# STM32F446ZEJx-SW308-UFO_V1_0.net
KiCad netlist of a schematic drawn in EAGLE
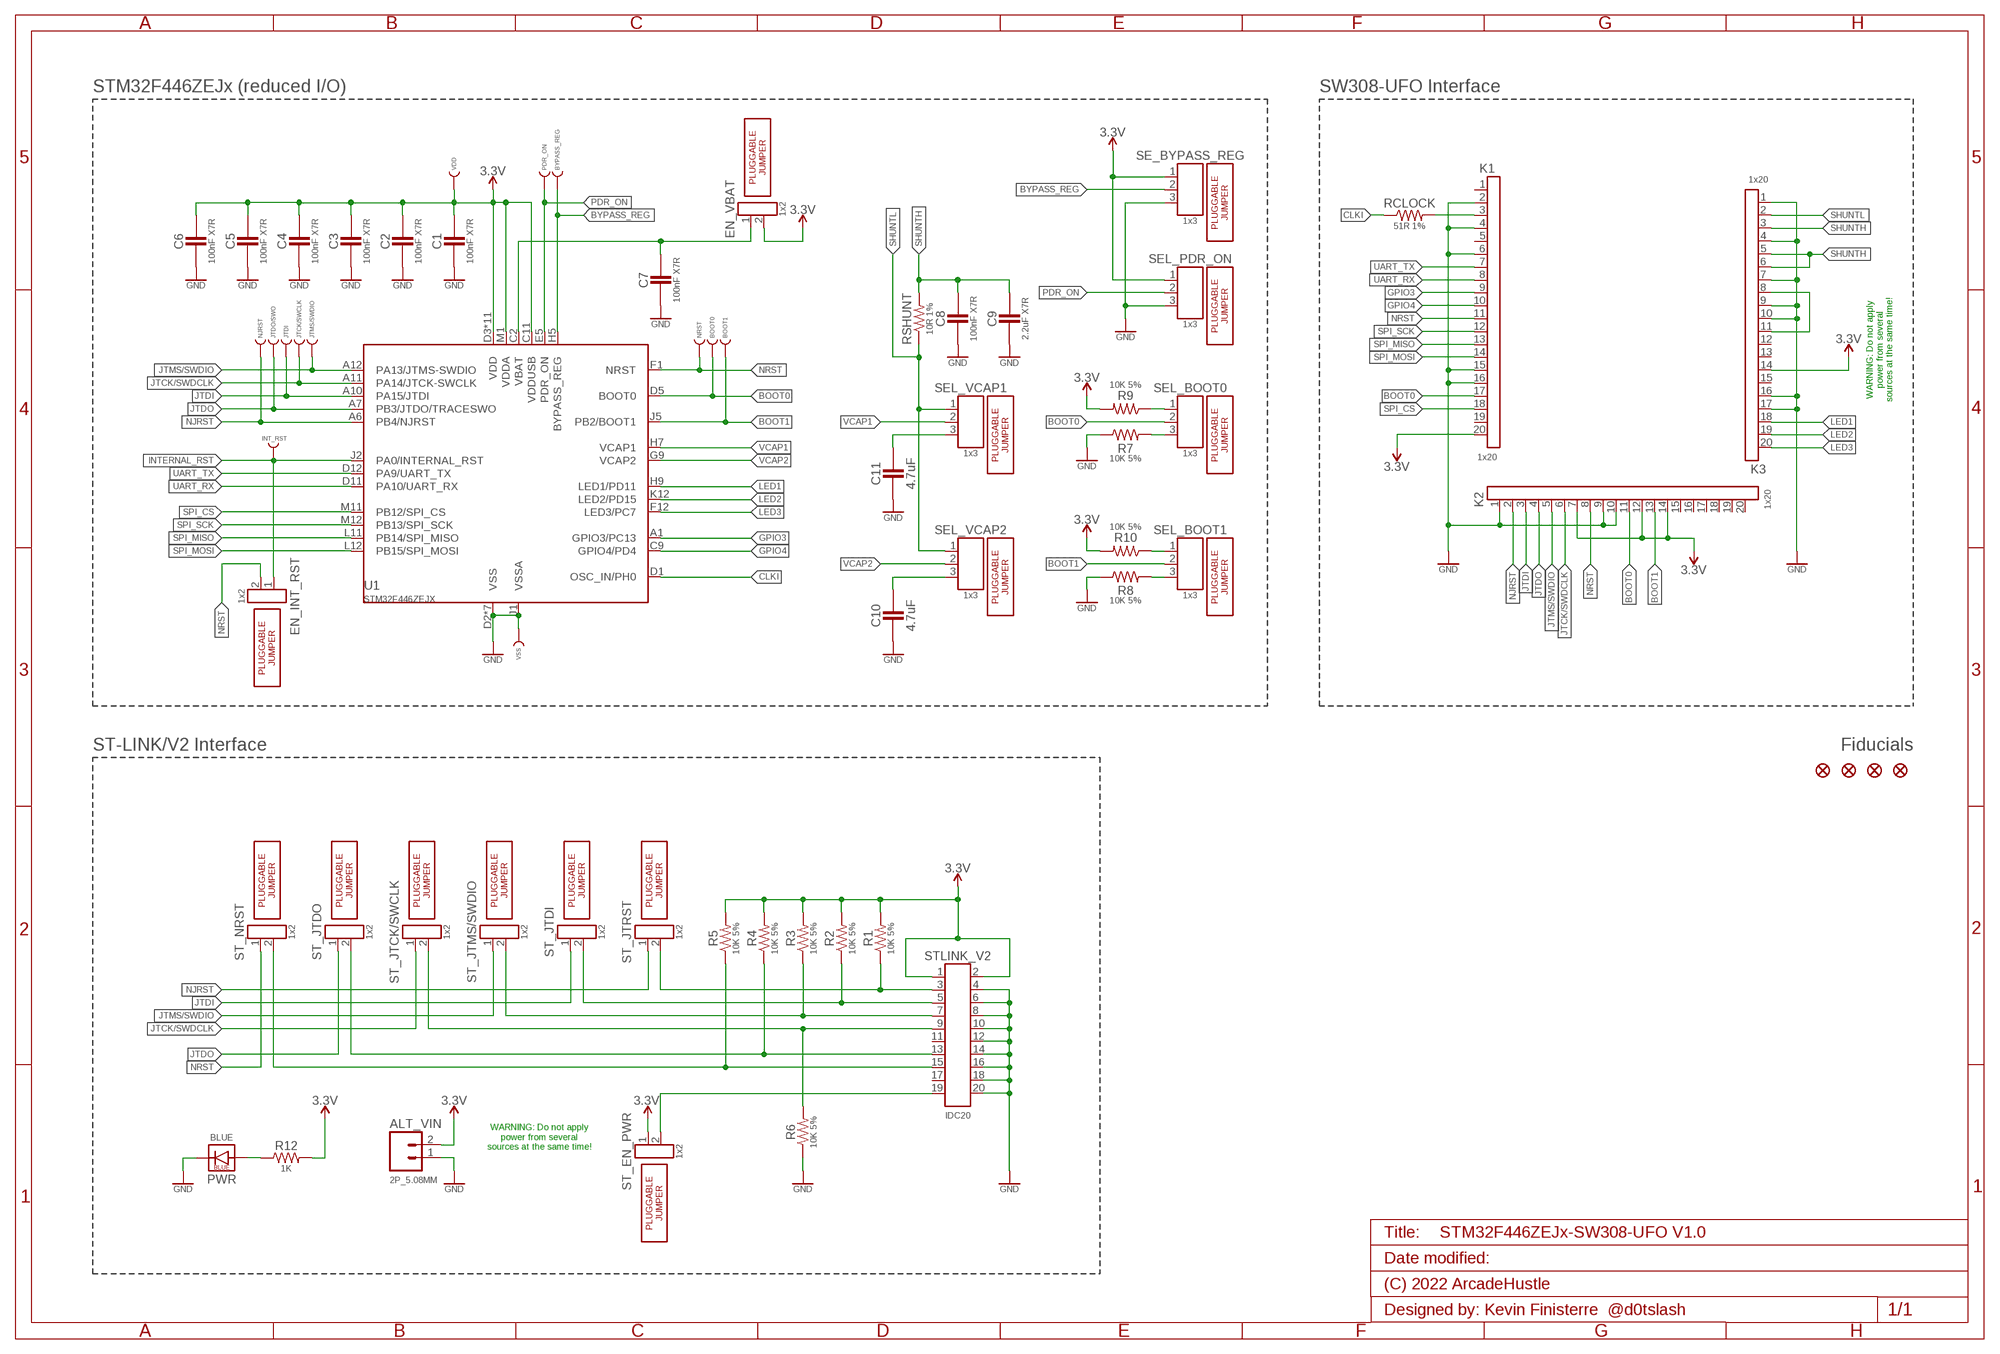
[diagram p0: schematic, sheet 1]

(export (version "E")
  (design (tool "Eeschema 10.0.6"))
  (components
    (comp (ref "ALT_VIN")
      (value "2P_5.08MM")
      (footprint "eagle-import:BORNA_2X5.08MM_NINGBO-KANGNEX-ELEC_WJ500V-5.08-2P")
      (fields (field (name "MANUFACTURER") "Ningbo Kangnex Elec"))
      (libsource (lib "eagle-import") (part "M02_BORNA_2X5.08MM_NINGBO-KANGNEX-ELEC_WJ500V-5.08-2P"))
    )
    (comp (ref "BOOT0")
      (value "TESTPOINT_TH_0.8MM")
      (footprint "eagle-import:1X01")
      (libsource (lib "eagle-import") (part "TESTPOINT_TH_0.8MM"))
    )
    (comp (ref "BOOT1")
      (value "TESTPOINT_TH_0.8MM")
      (footprint "eagle-import:1X01")
      (libsource (lib "eagle-import") (part "TESTPOINT_TH_0.8MM"))
    )
    (comp (ref "BYPASS_REG")
      (value "TESTPOINT_TH_0.8MM")
      (footprint "eagle-import:1X01")
      (libsource (lib "eagle-import") (part "TESTPOINT_TH_0.8MM"))
    )
    (comp (ref "C1")
      (value "100nF X7R")
      (footprint "eagle-import:0603_IPC_NOMINAL")
      (fields (field (name "MANUFACTURER") "Samsung Electro-Mechanics"))
      (libsource (lib "eagle-import") (part "CAP__0603_IPC_NOMINAL"))
    )
    (comp (ref "C2")
      (value "100nF X7R")
      (footprint "eagle-import:0603_IPC_NOMINAL")
      (fields (field (name "MANUFACTURER") "Samsung Electro-Mechanics"))
      (libsource (lib "eagle-import") (part "CAP__0603_IPC_NOMINAL"))
    )
    (comp (ref "C3")
      (value "100nF X7R")
      (footprint "eagle-import:0603_IPC_NOMINAL")
      (fields (field (name "MANUFACTURER") "Samsung Electro-Mechanics"))
      (libsource (lib "eagle-import") (part "CAP__0603_IPC_NOMINAL"))
    )
    (comp (ref "C4")
      (value "100nF X7R")
      (footprint "eagle-import:0603_IPC_NOMINAL")
      (fields (field (name "MANUFACTURER") "Samsung Electro-Mechanics"))
      (libsource (lib "eagle-import") (part "CAP__0603_IPC_NOMINAL"))
    )
    (comp (ref "C5")
      (value "100nF X7R")
      (footprint "eagle-import:0603_IPC_NOMINAL")
      (fields (field (name "MANUFACTURER") "Samsung Electro-Mechanics"))
      (libsource (lib "eagle-import") (part "CAP__0603_IPC_NOMINAL"))
    )
    (comp (ref "C6")
      (value "100nF X7R")
      (footprint "eagle-import:0603_IPC_NOMINAL")
      (fields (field (name "MANUFACTURER") "Samsung Electro-Mechanics"))
      (libsource (lib "eagle-import") (part "CAP__0603_IPC_NOMINAL"))
    )
    (comp (ref "C7")
      (value "100nF X7R")
      (footprint "eagle-import:0603_IPC_NOMINAL")
      (fields (field (name "MANUFACTURER") "Samsung Electro-Mechanics"))
      (libsource (lib "eagle-import") (part "CAP__0603_IPC_NOMINAL"))
    )
    (comp (ref "C8")
      (value "100nF X7R")
      (footprint "eagle-import:0603_IPC_NOMINAL")
      (fields (field (name "MANUFACTURER") "Samsung Electro-Mechanics"))
      (libsource (lib "eagle-import") (part "CAP__0603_IPC_NOMINAL"))
    )
    (comp (ref "C9")
      (value "2.2uF X7R")
      (footprint "eagle-import:0603_IPC_NOMINAL")
      (fields (field (name "MANUFACTURER") "Samsung Electro-Mechanics"))
      (libsource (lib "eagle-import") (part "CAP__0603_IPC_NOMINAL"))
    )
    (comp (ref "C10")
      (value "4.7uF")
      (footprint "eagle-import:0603_IPC_NOMINAL")
      (fields (field (name "MANUFACTURER") "Samsung Electro-Mechanics"))
      (libsource (lib "eagle-import") (part "CAP__0603_IPC_NOMINAL"))
    )
    (comp (ref "C11")
      (value "4.7uF")
      (footprint "eagle-import:0603_IPC_NOMINAL")
      (fields (field (name "MANUFACTURER") "Samsung Electro-Mechanics"))
      (libsource (lib "eagle-import") (part "CAP__0603_IPC_NOMINAL"))
    )
    (comp (ref "EN_INT_RST")
      (value "1x2")
      (footprint "eagle-import:M1X2_GREENCONN_GPHA101-0201A001A1BA(A=6,B=3)_ALT_PADS")
      (fields (field (name "MANUFACTURER") "Ckmtw(Shenzhen Cankemeng)"))
      (libsource (lib "eagle-import") (part "M1X2_GREENCONN_GPHA101-0201A001A1BA(A=6,B=3)_ALT_PADS"))
    )
    (comp (ref "EN_VBAT")
      (value "1x2")
      (footprint "eagle-import:M1X2_GREENCONN_GPHA101-0201A001A1BA(A=6,B=3)_ALT_PADS")
      (fields (field (name "MANUFACTURER") "Ckmtw(Shenzhen Cankemeng)"))
      (libsource (lib "eagle-import") (part "M1X2_GREENCONN_GPHA101-0201A001A1BA(A=6,B=3)_ALT_PADS"))
    )
    (comp (ref "FD1")
      (value "FIDUCIAL_MICRO")
      (footprint "eagle-import:FIDUCIAL-MICRO")
      (libsource (lib "eagle-import") (part "FIDUCIAL_MICRO"))
    )
    (comp (ref "FD5")
      (value "FIDUCIAL_MICRO")
      (footprint "eagle-import:FIDUCIAL-MICRO")
      (libsource (lib "eagle-import") (part "FIDUCIAL_MICRO"))
    )
    (comp (ref "FD7")
      (value "FIDUCIAL_MICRO")
      (footprint "eagle-import:FIDUCIAL-MICRO")
      (libsource (lib "eagle-import") (part "FIDUCIAL_MICRO"))
    )
    (comp (ref "FD9")
      (value "FIDUCIAL_MICRO")
      (footprint "eagle-import:FIDUCIAL-MICRO")
      (libsource (lib "eagle-import") (part "FIDUCIAL_MICRO"))
    )
    (comp (ref "INT_RST")
      (value "TESTPOINT_TH_0.8MM")
      (footprint "eagle-import:1X01")
      (libsource (lib "eagle-import") (part "TESTPOINT_TH_0.8MM"))
    )
    (comp (ref "JTCK/SWCLK")
      (value "TESTPOINT_TH_0.8MM")
      (footprint "eagle-import:1X01")
      (libsource (lib "eagle-import") (part "TESTPOINT_TH_0.8MM"))
    )
    (comp (ref "JTDI")
      (value "TESTPOINT_TH_0.8MM")
      (footprint "eagle-import:1X01")
      (libsource (lib "eagle-import") (part "TESTPOINT_TH_0.8MM"))
    )
    (comp (ref "JTDO/SWO")
      (value "TESTPOINT_TH_0.8MM")
      (footprint "eagle-import:1X01")
      (libsource (lib "eagle-import") (part "TESTPOINT_TH_0.8MM"))
    )
    (comp (ref "JTMS/SWDIO")
      (value "TESTPOINT_TH_0.8MM")
      (footprint "eagle-import:1X01")
      (libsource (lib "eagle-import") (part "TESTPOINT_TH_0.8MM"))
    )
    (comp (ref "JUMPER1")
      (value "JUMPER_2.54MM")
      (footprint "eagle-import:JUMPER_2.54MM")
      (fields (field (name "MANUFACTURER") "BOOMELE(Boom Precision Elec)"))
      (libsource (lib "eagle-import") (part "JUMPER_2.54MM"))
    )
    (comp (ref "JUMPER2")
      (value "JUMPER_2.54MM")
      (footprint "eagle-import:JUMPER_2.54MM")
      (fields (field (name "MANUFACTURER") "BOOMELE(Boom Precision Elec)"))
      (libsource (lib "eagle-import") (part "JUMPER_2.54MM"))
    )
    (comp (ref "JUMPER3")
      (value "JUMPER_2.54MM")
      (footprint "eagle-import:JUMPER_2.54MM")
      (fields (field (name "MANUFACTURER") "BOOMELE(Boom Precision Elec)"))
      (libsource (lib "eagle-import") (part "JUMPER_2.54MM"))
    )
    (comp (ref "JUMPER4")
      (value "JUMPER_2.54MM")
      (footprint "eagle-import:JUMPER_2.54MM")
      (fields (field (name "MANUFACTURER") "BOOMELE(Boom Precision Elec)"))
      (libsource (lib "eagle-import") (part "JUMPER_2.54MM"))
    )
    (comp (ref "JUMPER5")
      (value "JUMPER_2.54MM")
      (footprint "eagle-import:JUMPER_2.54MM")
      (fields (field (name "MANUFACTURER") "BOOMELE(Boom Precision Elec)"))
      (libsource (lib "eagle-import") (part "JUMPER_2.54MM"))
    )
    (comp (ref "JUMPER6")
      (value "JUMPER_2.54MM")
      (footprint "eagle-import:JUMPER_2.54MM")
      (fields (field (name "MANUFACTURER") "BOOMELE(Boom Precision Elec)"))
      (libsource (lib "eagle-import") (part "JUMPER_2.54MM"))
    )
    (comp (ref "JUMPER7")
      (value "JUMPER_2.54MM")
      (footprint "eagle-import:JUMPER_2.54MM")
      (fields (field (name "MANUFACTURER") "BOOMELE(Boom Precision Elec)"))
      (libsource (lib "eagle-import") (part "JUMPER_2.54MM"))
    )
    (comp (ref "JUMPER8")
      (value "JUMPER_2.54MM")
      (footprint "eagle-import:JUMPER_2.54MM")
      (fields (field (name "MANUFACTURER") "BOOMELE(Boom Precision Elec)"))
      (libsource (lib "eagle-import") (part "JUMPER_2.54MM"))
    )
    (comp (ref "JUMPER9")
      (value "JUMPER_2.54MM")
      (footprint "eagle-import:JUMPER_2.54MM")
      (fields (field (name "MANUFACTURER") "BOOMELE(Boom Precision Elec)"))
      (libsource (lib "eagle-import") (part "JUMPER_2.54MM"))
    )
    (comp (ref "JUMPER10")
      (value "JUMPER_2.54MM")
      (footprint "eagle-import:JUMPER_2.54MM")
      (fields (field (name "MANUFACTURER") "BOOMELE(Boom Precision Elec)"))
      (libsource (lib "eagle-import") (part "JUMPER_2.54MM"))
    )
    (comp (ref "JUMPER11")
      (value "JUMPER_2.54MM")
      (footprint "eagle-import:JUMPER_2.54MM")
      (fields (field (name "MANUFACTURER") "BOOMELE(Boom Precision Elec)"))
      (libsource (lib "eagle-import") (part "JUMPER_2.54MM"))
    )
    (comp (ref "JUMPER12")
      (value "JUMPER_2.54MM")
      (footprint "eagle-import:JUMPER_2.54MM")
      (fields (field (name "MANUFACTURER") "BOOMELE(Boom Precision Elec)"))
      (libsource (lib "eagle-import") (part "JUMPER_2.54MM"))
    )
    (comp (ref "JUMPER13")
      (value "JUMPER_2.54MM")
      (footprint "eagle-import:JUMPER_2.54MM")
      (fields (field (name "MANUFACTURER") "BOOMELE(Boom Precision Elec)"))
      (libsource (lib "eagle-import") (part "JUMPER_2.54MM"))
    )
    (comp (ref "JUMPER14")
      (value "JUMPER_2.54MM")
      (footprint "eagle-import:JUMPER_2.54MM")
      (fields (field (name "MANUFACTURER") "BOOMELE(Boom Precision Elec)"))
      (libsource (lib "eagle-import") (part "JUMPER_2.54MM"))
    )
    (comp (ref "JUMPER15")
      (value "JUMPER_2.54MM")
      (footprint "eagle-import:JUMPER_2.54MM")
      (fields (field (name "MANUFACTURER") "BOOMELE(Boom Precision Elec)"))
      (libsource (lib "eagle-import") (part "JUMPER_2.54MM"))
    )
    (comp (ref "K1")
      (value "1x20")
      (footprint "eagle-import:M1X20_2.54MM_LOCK_BOOMELE_C50981")
      (fields (field (name "MANUFACTURER") "BOOMELE(Boom Precision Elec)"))
      (libsource (lib "eagle-import") (part "M1X20_2.54MM_LOCK_BOOMELE_C50981"))
    )
    (comp (ref "K2")
      (value "1x20")
      (footprint "eagle-import:M1X20_2.54MM_LOCK_BOOMELE_C50981")
      (fields (field (name "MANUFACTURER") "BOOMELE(Boom Precision Elec)"))
      (libsource (lib "eagle-import") (part "M1X20_2.54MM_LOCK_BOOMELE_C50981"))
    )
    (comp (ref "K3")
      (value "1x20")
      (footprint "eagle-import:M1X20_2.54MM_LOCK_BOOMELE_C50981")
      (fields (field (name "MANUFACTURER") "BOOMELE(Boom Precision Elec)"))
      (libsource (lib "eagle-import") (part "M1X20_2.54MM_LOCK_BOOMELE_C50981"))
    )
    (comp (ref "NJRST")
      (value "TESTPOINT_TH_0.8MM")
      (footprint "eagle-import:1X01")
      (libsource (lib "eagle-import") (part "TESTPOINT_TH_0.8MM"))
    )
    (comp (ref "NRST")
      (value "TESTPOINT_TH_0.8MM")
      (footprint "eagle-import:1X01")
      (libsource (lib "eagle-import") (part "TESTPOINT_TH_0.8MM"))
    )
    (comp (ref "PDR_ON")
      (value "TESTPOINT_TH_0.8MM")
      (footprint "eagle-import:1X01")
      (libsource (lib "eagle-import") (part "TESTPOINT_TH_0.8MM"))
    )
    (comp (ref "PWR")
      (value "BLUE")
      (footprint "eagle-import:0603-BLUE-LED")
      (fields (field (name "MANUFACTURER") "Everlight Elec"))
      (libsource (lib "eagle-import") (part "DIODE-BLUE_0603"))
    )
    (comp (ref "R1")
      (value "10K 5%")
      (footprint "eagle-import:0603_IPC_NOMINAL")
      (fields (field (name "MANUFACTURER") "YAGEO"))
      (libsource (lib "eagle-import") (part "R_US_0603_IPC_NOMINAL"))
    )
    (comp (ref "R2")
      (value "10K 5%")
      (footprint "eagle-import:0603_IPC_NOMINAL")
      (fields (field (name "MANUFACTURER") "YAGEO"))
      (libsource (lib "eagle-import") (part "R_US_0603_IPC_NOMINAL"))
    )
    (comp (ref "R3")
      (value "10K 5%")
      (footprint "eagle-import:0603_IPC_NOMINAL")
      (fields (field (name "MANUFACTURER") "YAGEO"))
      (libsource (lib "eagle-import") (part "R_US_0603_IPC_NOMINAL"))
    )
    (comp (ref "R4")
      (value "10K 5%")
      (footprint "eagle-import:0603_IPC_NOMINAL")
      (fields (field (name "MANUFACTURER") "YAGEO"))
      (libsource (lib "eagle-import") (part "R_US_0603_IPC_NOMINAL"))
    )
    (comp (ref "R5")
      (value "10K 5%")
      (footprint "eagle-import:0603_IPC_NOMINAL")
      (fields (field (name "MANUFACTURER") "YAGEO"))
      (libsource (lib "eagle-import") (part "R_US_0603_IPC_NOMINAL"))
    )
    (comp (ref "R6")
      (value "10K 5%")
      (footprint "eagle-import:0603_IPC_NOMINAL")
      (fields (field (name "MANUFACTURER") "YAGEO"))
      (libsource (lib "eagle-import") (part "R_US_0603_IPC_NOMINAL"))
    )
    (comp (ref "R7")
      (value "10K 5%")
      (footprint "eagle-import:0603_IPC_NOMINAL")
      (fields (field (name "MANUFACTURER") "YAGEO"))
      (libsource (lib "eagle-import") (part "R_US_0603_IPC_NOMINAL"))
    )
    (comp (ref "R8")
      (value "10K 5%")
      (footprint "eagle-import:0603_IPC_NOMINAL")
      (fields (field (name "MANUFACTURER") "YAGEO"))
      (libsource (lib "eagle-import") (part "R_US_0603_IPC_NOMINAL"))
    )
    (comp (ref "R9")
      (value "10K 5%")
      (footprint "eagle-import:0603_IPC_NOMINAL")
      (fields (field (name "MANUFACTURER") "YAGEO"))
      (libsource (lib "eagle-import") (part "R_US_0603_IPC_NOMINAL"))
    )
    (comp (ref "R10")
      (value "10K 5%")
      (footprint "eagle-import:0603_IPC_NOMINAL")
      (fields (field (name "MANUFACTURER") "YAGEO"))
      (libsource (lib "eagle-import") (part "R_US_0603_IPC_NOMINAL"))
    )
    (comp (ref "R12")
      (value "1K")
      (footprint "eagle-import:0603_IPC_NOMINAL")
      (fields (field (name "MANUFACTURER") "YAGEO"))
      (libsource (lib "eagle-import") (part "R_US_0603_IPC_NOMINAL"))
    )
    (comp (ref "RCLOCK")
      (value "51R 1%")
      (footprint "eagle-import:0603_IPC_NOMINAL")
      (fields (field (name "MANUFACTURER") "YAGEO"))
      (libsource (lib "eagle-import") (part "R_US_0603_IPC_NOMINAL"))
    )
    (comp (ref "RSHUNT")
      (value "10R 1%")
      (footprint "eagle-import:0603_IPC_NOMINAL")
      (fields (field (name "MANUFACTURER") "YAGEO"))
      (libsource (lib "eagle-import") (part "R_US_0603_IPC_NOMINAL"))
    )
    (comp (ref "SEL_BOOT0")
      (value "1x3")
      (footprint "eagle-import:M1X3_GREENCONN_GPHA101-0301A001A1BA(A=6,B=3)_ALT_PADS")
      (fields (field (name "MANUFACTURER") "BOOMELE(Boom Precision Elec)"))
      (libsource (lib "eagle-import") (part "M3_GREENCONN_GPHA101-0301A001A1BA(A=6,B=3)_ALT_PADS"))
    )
    (comp (ref "SEL_BOOT1")
      (value "1x3")
      (footprint "eagle-import:M1X3_GREENCONN_GPHA101-0301A001A1BA(A=6,B=3)_ALT_PADS")
      (fields (field (name "MANUFACTURER") "BOOMELE(Boom Precision Elec)"))
      (libsource (lib "eagle-import") (part "M3_GREENCONN_GPHA101-0301A001A1BA(A=6,B=3)_ALT_PADS"))
    )
    (comp (ref "SEL_PDR_ON")
      (value "1x3")
      (footprint "eagle-import:M1X3_GREENCONN_GPHA101-0301A001A1BA(A=6,B=3)_ALT_PADS")
      (fields (field (name "MANUFACTURER") "BOOMELE(Boom Precision Elec)"))
      (libsource (lib "eagle-import") (part "M3_GREENCONN_GPHA101-0301A001A1BA(A=6,B=3)_ALT_PADS"))
    )
    (comp (ref "SEL_VCAP1")
      (value "1x3")
      (footprint "eagle-import:M1X3_GREENCONN_GPHA101-0301A001A1BA(A=6,B=3)_ALT_PADS")
      (fields (field (name "MANUFACTURER") "BOOMELE(Boom Precision Elec)"))
      (libsource (lib "eagle-import") (part "M3_GREENCONN_GPHA101-0301A001A1BA(A=6,B=3)_ALT_PADS"))
    )
    (comp (ref "SEL_VCAP2")
      (value "1x3")
      (footprint "eagle-import:M1X3_GREENCONN_GPHA101-0301A001A1BA(A=6,B=3)_ALT_PADS")
      (fields (field (name "MANUFACTURER") "BOOMELE(Boom Precision Elec)"))
      (libsource (lib "eagle-import") (part "M3_GREENCONN_GPHA101-0301A001A1BA(A=6,B=3)_ALT_PADS"))
    )
    (comp (ref "SE_BYPASS_REG")
      (value "1x3")
      (footprint "eagle-import:M1X3_GREENCONN_GPHA101-0301A001A1BA(A=6,B=3)_ALT_PADS")
      (fields (field (name "MANUFACTURER") "BOOMELE(Boom Precision Elec)"))
      (libsource (lib "eagle-import") (part "M3_GREENCONN_GPHA101-0301A001A1BA(A=6,B=3)_ALT_PADS"))
    )
    (comp (ref "STLINK_V2")
      (value "IDC20")
      (footprint "eagle-import:M2X10_2.54MM_IDC_SHROUDED__JLIN_321020SG0ABK00A01_C429961")
      (fields (field (name "MANUFACTURER") "JLIN"))
      (libsource (lib "eagle-import") (part "M2X10_2.54MM_IDC_SHROUDED__JLIN_321020SG0ABK00A01_C429961"))
    )
    (comp (ref "ST_EN_PWR")
      (value "1x2")
      (footprint "eagle-import:M1X2_GREENCONN_GPHA101-0201A001A1BA(A=6,B=3)_ALT_PADS")
      (fields (field (name "MANUFACTURER") "Ckmtw(Shenzhen Cankemeng)"))
      (libsource (lib "eagle-import") (part "M1X2_GREENCONN_GPHA101-0201A001A1BA(A=6,B=3)_ALT_PADS"))
    )
    (comp (ref "ST_JTCK/SWCLK")
      (value "1x2")
      (footprint "eagle-import:M1X2_GREENCONN_GPHA101-0201A001A1BA(A=6,B=3)_ALT_PADS")
      (fields (field (name "MANUFACTURER") "Ckmtw(Shenzhen Cankemeng)"))
      (libsource (lib "eagle-import") (part "M1X2_GREENCONN_GPHA101-0201A001A1BA(A=6,B=3)_ALT_PADS"))
    )
    (comp (ref "ST_JTDI")
      (value "1x2")
      (footprint "eagle-import:M1X2_GREENCONN_GPHA101-0201A001A1BA(A=6,B=3)_ALT_PADS")
      (fields (field (name "MANUFACTURER") "Ckmtw(Shenzhen Cankemeng)"))
      (libsource (lib "eagle-import") (part "M1X2_GREENCONN_GPHA101-0201A001A1BA(A=6,B=3)_ALT_PADS"))
    )
    (comp (ref "ST_JTDO")
      (value "1x2")
      (footprint "eagle-import:M1X2_GREENCONN_GPHA101-0201A001A1BA(A=6,B=3)_ALT_PADS")
      (fields (field (name "MANUFACTURER") "Ckmtw(Shenzhen Cankemeng)"))
      (libsource (lib "eagle-import") (part "M1X2_GREENCONN_GPHA101-0201A001A1BA(A=6,B=3)_ALT_PADS"))
    )
    (comp (ref "ST_JTMS/SWDIO")
      (value "1x2")
      (footprint "eagle-import:M1X2_GREENCONN_GPHA101-0201A001A1BA(A=6,B=3)_ALT_PADS")
      (fields (field (name "MANUFACTURER") "Ckmtw(Shenzhen Cankemeng)"))
      (libsource (lib "eagle-import") (part "M1X2_GREENCONN_GPHA101-0201A001A1BA(A=6,B=3)_ALT_PADS"))
    )
    (comp (ref "ST_JTRST")
      (value "1x2")
      (footprint "eagle-import:M1X2_GREENCONN_GPHA101-0201A001A1BA(A=6,B=3)_ALT_PADS")
      (fields (field (name "MANUFACTURER") "Ckmtw(Shenzhen Cankemeng)"))
      (libsource (lib "eagle-import") (part "M1X2_GREENCONN_GPHA101-0201A001A1BA(A=6,B=3)_ALT_PADS"))
    )
    (comp (ref "ST_NRST")
      (value "1x2")
      (footprint "eagle-import:M1X2_GREENCONN_GPHA101-0201A001A1BA(A=6,B=3)_ALT_PADS")
      (fields (field (name "MANUFACTURER") "Ckmtw(Shenzhen Cankemeng)"))
      (libsource (lib "eagle-import") (part "M1X2_GREENCONN_GPHA101-0201A001A1BA(A=6,B=3)_ALT_PADS"))
    )
    (comp (ref "U1")
      (value "STM32F446ZEJX")
      (footprint "eagle-import:STM32F446ZEJX")
      (libsource (lib "eagle-import") (part "STM32F446ZEJX_MINIMUM2_UFBGA144"))
    )
    (comp (ref "VDD")
      (value "TESTPOINT_TH_0.8MM")
      (footprint "eagle-import:1X01")
      (libsource (lib "eagle-import") (part "TESTPOINT_TH_0.8MM"))
    )
    (comp (ref "VSS")
      (value "TESTPOINT_TH_0.8MM")
      (footprint "eagle-import:1X01")
      (libsource (lib "eagle-import") (part "TESTPOINT_TH_0.8MM"))
    )
  )
  (nets
    (net (code "1") (name "3.3V") (class "Default")
      (node (ref "ALT_VIN") (pin "2") (pinfunction "2_2") (pintype "passive"))
      (node (ref "C1") (pin "1") (pinfunction "1_1") (pintype "passive"))
      (node (ref "C2") (pin "1") (pinfunction "1_1") (pintype "passive"))
      (node (ref "C3") (pin "1") (pinfunction "1_1") (pintype "passive"))
      (node (ref "C4") (pin "1") (pinfunction "1_1") (pintype "passive"))
      (node (ref "C5") (pin "1") (pinfunction "1_1") (pintype "passive"))
      (node (ref "C6") (pin "1") (pinfunction "1_1") (pintype "passive"))
      (node (ref "EN_VBAT") (pin "2") (pinfunction "2_2") (pintype "bidirectional"))
      (node (ref "K1") (pin "20") (pinfunction "20_20") (pintype "bidirectional"))
      (node (ref "K2") (pin "12") (pinfunction "12_12") (pintype "bidirectional"))
      (node (ref "K2") (pin "14") (pinfunction "14_14") (pintype "bidirectional"))
      (node (ref "K2") (pin "7") (pinfunction "7_7") (pintype "bidirectional"))
      (node (ref "K3") (pin "14") (pinfunction "14_14") (pintype "bidirectional"))
      (node (ref "R1") (pin "2") (pinfunction "2_2") (pintype "passive"))
      (node (ref "R10") (pin "2") (pinfunction "2_2") (pintype "passive"))
      (node (ref "R12") (pin "2") (pinfunction "2_2") (pintype "passive"))
      (node (ref "R2") (pin "2") (pinfunction "2_2") (pintype "passive"))
      (node (ref "R3") (pin "2") (pinfunction "2_2") (pintype "passive"))
      (node (ref "R4") (pin "2") (pinfunction "2_2") (pintype "passive"))
      (node (ref "R5") (pin "2") (pinfunction "2_2") (pintype "passive"))
      (node (ref "R9") (pin "2") (pinfunction "2_2") (pintype "passive"))
      (node (ref "SEL_PDR_ON") (pin "1") (pinfunction "1_1") (pintype "bidirectional"))
      (node (ref "SE_BYPASS_REG") (pin "1") (pinfunction "1_1") (pintype "bidirectional"))
      (node (ref "STLINK_V2") (pin "1") (pinfunction "1_1") (pintype "bidirectional"))
      (node (ref "STLINK_V2") (pin "2") (pinfunction "2_2") (pintype "bidirectional"))
      (node (ref "ST_EN_PWR") (pin "1") (pinfunction "1_1") (pintype "bidirectional"))
      (node (ref "U1") (pin "C11") (pinfunction "VDDUSB_C11") (pintype "power_in"))
      (node (ref "U1") (pin "D3") (pinfunction "VDD_D3") (pintype "power_in"))
      (node (ref "U1") (pin "F10") (pinfunction "VDD_F10") (pintype "power_in"))
      (node (ref "U1") (pin "F4") (pinfunction "VDD_F4") (pintype "power_in"))
      (node (ref "U1") (pin "F5") (pinfunction "VDD_F5") (pintype "power_in"))
      (node (ref "U1") (pin "F6") (pinfunction "VDD_F6") (pintype "power_in"))
      (node (ref "U1") (pin "F7") (pinfunction "VDD_F7") (pintype "power_in"))
      (node (ref "U1") (pin "F8") (pinfunction "VDD_F8") (pintype "power_in"))
      (node (ref "U1") (pin "F9") (pinfunction "VDD_F9") (pintype "power_in"))
      (node (ref "U1") (pin "G5") (pinfunction "VDD_G5") (pintype "power_in"))
      (node (ref "U1") (pin "G6") (pinfunction "VDD_G6") (pintype "power_in"))
      (node (ref "U1") (pin "G7") (pinfunction "VDD_G7") (pintype "power_in"))
      (node (ref "U1") (pin "M1") (pinfunction "VDDA_M1") (pintype "power_in"))
      (node (ref "VDD") (pin "1") (pinfunction "1_1") (pintype "bidirectional"))
    )
    (net (code "2") (name "BOOT0") (class "Default")
      (node (ref "BOOT0") (pin "1") (pinfunction "1_1") (pintype "bidirectional"))
      (node (ref "K1") (pin "17") (pinfunction "17_17") (pintype "bidirectional"))
      (node (ref "K2") (pin "11") (pinfunction "11_11") (pintype "bidirectional"))
      (node (ref "SEL_BOOT0") (pin "2") (pinfunction "2_2") (pintype "bidirectional"))
      (node (ref "U1") (pin "D5") (pinfunction "BOOT0_D5") (pintype "bidirectional"))
    )
    (net (code "3") (name "BOOT1") (class "Default")
      (node (ref "BOOT1") (pin "1") (pinfunction "1_1") (pintype "bidirectional"))
      (node (ref "K2") (pin "13") (pinfunction "13_13") (pintype "bidirectional"))
      (node (ref "SEL_BOOT1") (pin "2") (pinfunction "2_2") (pintype "bidirectional"))
      (node (ref "U1") (pin "J5") (pinfunction "PB2/BOOT1_J5") (pintype "bidirectional"))
    )
    (net (code "4") (name "BYPASS_REG") (class "Default")
      (node (ref "BYPASS_REG") (pin "1") (pinfunction "1_1") (pintype "bidirectional"))
      (node (ref "SE_BYPASS_REG") (pin "2") (pinfunction "2_2") (pintype "bidirectional"))
      (node (ref "U1") (pin "H5") (pinfunction "BYPASS_REG_H5") (pintype "power_in"))
    )
    (net (code "5") (name "CLKI") (class "Default")
      (node (ref "RCLOCK") (pin "1") (pinfunction "1_1") (pintype "passive"))
      (node (ref "U1") (pin "D1") (pinfunction "OSC_IN/PH0_D1") (pintype "bidirectional"))
    )
    (net (code "6") (name "GND") (class "Default")
      (node (ref "ALT_VIN") (pin "1") (pinfunction "1_1") (pintype "passive"))
      (node (ref "C1") (pin "2") (pinfunction "2_2") (pintype "passive"))
      (node (ref "C10") (pin "2") (pinfunction "2_2") (pintype "passive"))
      (node (ref "C11") (pin "2") (pinfunction "2_2") (pintype "passive"))
      (node (ref "C2") (pin "2") (pinfunction "2_2") (pintype "passive"))
      (node (ref "C3") (pin "2") (pinfunction "2_2") (pintype "passive"))
      (node (ref "C4") (pin "2") (pinfunction "2_2") (pintype "passive"))
      (node (ref "C5") (pin "2") (pinfunction "2_2") (pintype "passive"))
      (node (ref "C6") (pin "2") (pinfunction "2_2") (pintype "passive"))
      (node (ref "C7") (pin "2") (pinfunction "2_2") (pintype "passive"))
      (node (ref "C8") (pin "2") (pinfunction "2_2") (pintype "passive"))
      (node (ref "C9") (pin "2") (pinfunction "2_2") (pintype "passive"))
      (node (ref "K1") (pin "15") (pinfunction "15_15") (pintype "bidirectional"))
      (node (ref "K1") (pin "16") (pinfunction "16_16") (pintype "bidirectional"))
      (node (ref "K1") (pin "2") (pinfunction "2_2") (pintype "bidirectional"))
      (node (ref "K1") (pin "4") (pinfunction "4_4") (pintype "bidirectional"))
      (node (ref "K1") (pin "6") (pinfunction "6_6") (pintype "bidirectional"))
      (node (ref "K2") (pin "1") (pinfunction "1_1") (pintype "bidirectional"))
      (node (ref "K2") (pin "10") (pinfunction "10_10") (pintype "bidirectional"))
      (node (ref "K2") (pin "9") (pinfunction "9_9") (pintype "bidirectional"))
      (node (ref "K3") (pin "1") (pinfunction "1_1") (pintype "bidirectional"))
      (node (ref "K3") (pin "10") (pinfunction "10_10") (pintype "bidirectional"))
      (node (ref "K3") (pin "16") (pinfunction "16_16") (pintype "bidirectional"))
      (node (ref "K3") (pin "17") (pinfunction "17_17") (pintype "bidirectional"))
      (node (ref "K3") (pin "4") (pinfunction "4_4") (pintype "bidirectional"))
      (node (ref "K3") (pin "7") (pinfunction "7_7") (pintype "bidirectional"))
      (node (ref "K3") (pin "9") (pinfunction "9_9") (pintype "bidirectional"))
      (node (ref "PWR") (pin "CATHODE") (pinfunction "C_CATHODE") (pintype "passive"))
      (node (ref "R6") (pin "1") (pinfunction "1_1") (pintype "passive"))
      (node (ref "R7") (pin "1") (pinfunction "1_1") (pintype "passive"))
      (node (ref "R8") (pin "1") (pinfunction "1_1") (pintype "passive"))
      (node (ref "SEL_PDR_ON") (pin "3") (pinfunction "3_3") (pintype "bidirectional"))
      (node (ref "SE_BYPASS_REG") (pin "3") (pinfunction "3_3") (pintype "bidirectional"))
      (node (ref "STLINK_V2") (pin "10") (pinfunction "10_10") (pintype "bidirectional"))
      (node (ref "STLINK_V2") (pin "12") (pinfunction "12_12") (pintype "bidirectional"))
      (node (ref "STLINK_V2") (pin "14") (pinfunction "14_14") (pintype "bidirectional"))
      (node (ref "STLINK_V2") (pin "16") (pinfunction "16_16") (pintype "bidirectional"))
      (node (ref "STLINK_V2") (pin "18") (pinfunction "18_18") (pintype "bidirectional"))
      (node (ref "STLINK_V2") (pin "20") (pinfunction "20_20") (pintype "bidirectional"))
      (node (ref "STLINK_V2") (pin "4") (pinfunction "4_4") (pintype "bidirectional"))
      (node (ref "STLINK_V2") (pin "6") (pinfunction "6_6") (pintype "bidirectional"))
      (node (ref "STLINK_V2") (pin "8") (pinfunction "8_8") (pintype "bidirectional"))
      (node (ref "U1") (pin "D2") (pinfunction "VSS_D2") (pintype "power_in"))
      (node (ref "U1") (pin "E6") (pinfunction "VSS_E6") (pintype "power_in"))
      (node (ref "U1") (pin "E7") (pinfunction "VSS_E7") (pintype "power_in"))
      (node (ref "U1") (pin "G10") (pinfunction "VSS_G10") (pintype "power_in"))
      (node (ref "U1") (pin "G4") (pinfunction "VSS_G4") (pintype "power_in"))
      (node (ref "U1") (pin "G8") (pinfunction "VSS_G8") (pintype "power_in"))
      (node (ref "U1") (pin "H6") (pinfunction "VSS_H6") (pintype "power_in"))
      (node (ref "U1") (pin "J1") (pinfunction "VSSA_J1") (pintype "power_in"))
      (node (ref "VSS") (pin "1") (pinfunction "1_1") (pintype "bidirectional"))
    )
    (net (code "7") (name "GPIO3") (class "Default")
      (node (ref "K1") (pin "9") (pinfunction "9_9") (pintype "bidirectional"))
      (node (ref "U1") (pin "A1") (pinfunction "GPIO3/PC13_A1") (pintype "bidirectional"))
    )
    (net (code "8") (name "GPIO4") (class "Default")
      (node (ref "K1") (pin "10") (pinfunction "10_10") (pintype "bidirectional"))
      (node (ref "U1") (pin "C9") (pinfunction "GPIO4/PD4_C9") (pintype "bidirectional"))
    )
    (net (code "9") (name "INTERNAL_RST") (class "Default")
      (node (ref "EN_INT_RST") (pin "1") (pinfunction "1_1") (pintype "bidirectional"))
      (node (ref "INT_RST") (pin "1") (pinfunction "1_1") (pintype "bidirectional"))
      (node (ref "U1") (pin "J2") (pinfunction "PA0/INTERNAL_RST_J2") (pintype "bidirectional"))
    )
    (net (code "10") (name "JTCK{slash}SWDCLK") (class "Default")
      (node (ref "JTCK/SWCLK") (pin "1") (pinfunction "1_1") (pintype "bidirectional"))
      (node (ref "K2") (pin "6") (pinfunction "6_6") (pintype "bidirectional"))
      (node (ref "ST_JTCK/SWCLK") (pin "1") (pinfunction "1_1") (pintype "bidirectional"))
      (node (ref "U1") (pin "A11") (pinfunction "PA14/JTCK-SWCLK_A11") (pintype "bidirectional"))
    )
    (net (code "11") (name "JTDI") (class "Default")
      (node (ref "JTDI") (pin "1") (pinfunction "1_1") (pintype "bidirectional"))
      (node (ref "K2") (pin "3") (pinfunction "3_3") (pintype "bidirectional"))
      (node (ref "ST_JTDI") (pin "1") (pinfunction "1_1") (pintype "bidirectional"))
      (node (ref "U1") (pin "A10") (pinfunction "PA15/JTDI_A10") (pintype "bidirectional"))
    )
    (net (code "12") (name "JTDO") (class "Default")
      (node (ref "JTDO/SWO") (pin "1") (pinfunction "1_1") (pintype "bidirectional"))
      (node (ref "K2") (pin "4") (pinfunction "4_4") (pintype "bidirectional"))
      (node (ref "ST_JTDO") (pin "1") (pinfunction "1_1") (pintype "bidirectional"))
      (node (ref "U1") (pin "A7") (pinfunction "PB3/JTDO/TRACESWO_A7") (pintype "bidirectional"))
    )
    (net (code "13") (name "JTMS{slash}SWDIO") (class "Default")
      (node (ref "JTMS/SWDIO") (pin "1") (pinfunction "1_1") (pintype "bidirectional"))
      (node (ref "K2") (pin "5") (pinfunction "5_5") (pintype "bidirectional"))
      (node (ref "ST_JTMS/SWDIO") (pin "1") (pinfunction "1_1") (pintype "bidirectional"))
      (node (ref "U1") (pin "A12") (pinfunction "PA13/JTMS-SWDIO_A12") (pintype "bidirectional"))
    )
    (net (code "14") (name "LED1") (class "Default")
      (node (ref "K3") (pin "18") (pinfunction "18_18") (pintype "bidirectional"))
      (node (ref "U1") (pin "H9") (pinfunction "LED1/PD11_H9") (pintype "bidirectional"))
    )
    (net (code "15") (name "LED2") (class "Default")
      (node (ref "K3") (pin "19") (pinfunction "19_19") (pintype "bidirectional"))
      (node (ref "U1") (pin "K12") (pinfunction "LED2/PD15_K12") (pintype "bidirectional"))
    )
    (net (code "16") (name "LED3") (class "Default")
      (node (ref "K3") (pin "20") (pinfunction "20_20") (pintype "bidirectional"))
      (node (ref "U1") (pin "F12") (pinfunction "LED3/PC7_F12") (pintype "bidirectional"))
    )
    (net (code "17") (name "NJRST") (class "Default")
      (node (ref "K2") (pin "2") (pinfunction "2_2") (pintype "bidirectional"))
      (node (ref "NJRST") (pin "1") (pinfunction "1_1") (pintype "bidirectional"))
      (node (ref "ST_JTRST") (pin "1") (pinfunction "1_1") (pintype "bidirectional"))
      (node (ref "U1") (pin "A6") (pinfunction "PB4/NJRST_A6") (pintype "bidirectional"))
    )
    (net (code "18") (name "NRST") (class "Default")
      (node (ref "EN_INT_RST") (pin "2") (pinfunction "2_2") (pintype "bidirectional"))
      (node (ref "K1") (pin "11") (pinfunction "11_11") (pintype "bidirectional"))
      (node (ref "K2") (pin "8") (pinfunction "8_8") (pintype "bidirectional"))
      (node (ref "NRST") (pin "1") (pinfunction "1_1") (pintype "bidirectional"))
      (node (ref "ST_NRST") (pin "1") (pinfunction "1_1") (pintype "bidirectional"))
      (node (ref "U1") (pin "F1") (pinfunction "NRST_F1") (pintype "bidirectional"))
    )
    (net (code "19") (name "Net-(C10-Pad1)") (class "Default")
      (node (ref "C10") (pin "1") (pinfunction "1_1") (pintype "passive"))
      (node (ref "SEL_VCAP2") (pin "3") (pinfunction "3_3") (pintype "bidirectional"))
    )
    (net (code "20") (name "Net-(C11-Pad1)") (class "Default")
      (node (ref "C11") (pin "1") (pinfunction "1_1") (pintype "passive"))
      (node (ref "SEL_VCAP1") (pin "3") (pinfunction "3_3") (pintype "bidirectional"))
    )
    (net (code "21") (name "Net-(K1-Pad3)") (class "Default")
      (node (ref "K1") (pin "3") (pinfunction "3_3") (pintype "bidirectional"))
      (node (ref "RCLOCK") (pin "2") (pinfunction "2_2") (pintype "passive"))
    )
    (net (code "22") (name "Net-(K3-Pad11)") (class "Default")
      (node (ref "K3") (pin "11") (pinfunction "11_11") (pintype "bidirectional"))
      (node (ref "K3") (pin "8") (pinfunction "8_8") (pintype "bidirectional"))
    )
    (net (code "23") (name "Net-(PWR-A)") (class "Default")
      (node (ref "PWR") (pin "ANODE") (pinfunction "A_ANODE") (pintype "passive"))
      (node (ref "R12") (pin "1") (pinfunction "1_1") (pintype "passive"))
    )
    (net (code "24") (name "Net-(R1-Pad1)") (class "Default")
      (node (ref "R1") (pin "1") (pinfunction "1_1") (pintype "passive"))
      (node (ref "STLINK_V2") (pin "3") (pinfunction "3_3") (pintype "bidirectional"))
      (node (ref "ST_JTRST") (pin "2") (pinfunction "2_2") (pintype "bidirectional"))
    )
    (net (code "25") (name "Net-(R2-Pad1)") (class "Default")
      (node (ref "R2") (pin "1") (pinfunction "1_1") (pintype "passive"))
      (node (ref "STLINK_V2") (pin "5") (pinfunction "5_5") (pintype "bidirectional"))
      (node (ref "ST_JTDI") (pin "2") (pinfunction "2_2") (pintype "bidirectional"))
    )
    (net (code "26") (name "Net-(R3-Pad1)") (class "Default")
      (node (ref "R3") (pin "1") (pinfunction "1_1") (pintype "passive"))
      (node (ref "STLINK_V2") (pin "7") (pinfunction "7_7") (pintype "bidirectional"))
      (node (ref "ST_JTMS/SWDIO") (pin "2") (pinfunction "2_2") (pintype "bidirectional"))
    )
    (net (code "27") (name "Net-(R4-Pad1)") (class "Default")
      (node (ref "R4") (pin "1") (pinfunction "1_1") (pintype "passive"))
      (node (ref "STLINK_V2") (pin "13") (pinfunction "13_13") (pintype "bidirectional"))
      (node (ref "ST_JTDO") (pin "2") (pinfunction "2_2") (pintype "bidirectional"))
    )
    (net (code "28") (name "Net-(R5-Pad1)") (class "Default")
      (node (ref "R5") (pin "1") (pinfunction "1_1") (pintype "passive"))
      (node (ref "STLINK_V2") (pin "15") (pinfunction "15_15") (pintype "bidirectional"))
      (node (ref "ST_NRST") (pin "2") (pinfunction "2_2") (pintype "bidirectional"))
    )
    (net (code "29") (name "Net-(R6-Pad2)") (class "Default")
      (node (ref "R6") (pin "2") (pinfunction "2_2") (pintype "passive"))
      (node (ref "STLINK_V2") (pin "9") (pinfunction "9_9") (pintype "bidirectional"))
      (node (ref "ST_JTCK/SWCLK") (pin "2") (pinfunction "2_2") (pintype "bidirectional"))
    )
    (net (code "30") (name "Net-(R7-Pad2)") (class "Default")
      (node (ref "R7") (pin "2") (pinfunction "2_2") (pintype "passive"))
      (node (ref "SEL_BOOT0") (pin "3") (pinfunction "3_3") (pintype "bidirectional"))
    )
    (net (code "31") (name "Net-(R8-Pad2)") (class "Default")
      (node (ref "R8") (pin "2") (pinfunction "2_2") (pintype "passive"))
      (node (ref "SEL_BOOT1") (pin "3") (pinfunction "3_3") (pintype "bidirectional"))
    )
    (net (code "32") (name "Net-(R9-Pad1)") (class "Default")
      (node (ref "R9") (pin "1") (pinfunction "1_1") (pintype "passive"))
      (node (ref "SEL_BOOT0") (pin "1") (pinfunction "1_1") (pintype "bidirectional"))
    )
    (net (code "33") (name "Net-(R10-Pad1)") (class "Default")
      (node (ref "R10") (pin "1") (pinfunction "1_1") (pintype "passive"))
      (node (ref "SEL_BOOT1") (pin "1") (pinfunction "1_1") (pintype "bidirectional"))
    )
    (net (code "34") (name "Net-(STLINK_V2-Pad19)") (class "Default")
      (node (ref "STLINK_V2") (pin "19") (pinfunction "19_19") (pintype "bidirectional"))
      (node (ref "ST_EN_PWR") (pin "2") (pinfunction "2_2") (pintype "bidirectional"))
    )
    (net (code "35") (name "Net-(U1-VBAT)") (class "Default")
      (node (ref "C7") (pin "1") (pinfunction "1_1") (pintype "passive"))
      (node (ref "EN_VBAT") (pin "1") (pinfunction "1_1") (pintype "bidirectional"))
      (node (ref "U1") (pin "C2") (pinfunction "VBAT_C2") (pintype "power_in"))
    )
    (net (code "36") (name "PDR_ON") (class "Default")
      (node (ref "PDR_ON") (pin "1") (pinfunction "1_1") (pintype "bidirectional"))
      (node (ref "SEL_PDR_ON") (pin "2") (pinfunction "2_2") (pintype "bidirectional"))
      (node (ref "U1") (pin "E5") (pinfunction "PDR_ON_E5") (pintype "power_in"))
    )
    (net (code "37") (name "SHUNTH") (class "Default")
      (node (ref "C8") (pin "1") (pinfunction "1_1") (pintype "passive"))
      (node (ref "C9") (pin "1") (pinfunction "1_1") (pintype "passive"))
      (node (ref "K3") (pin "3") (pinfunction "3_3") (pintype "bidirectional"))
      (node (ref "K3") (pin "5") (pinfunction "5_5") (pintype "bidirectional"))
      (node (ref "K3") (pin "6") (pinfunction "6_6") (pintype "bidirectional"))
      (node (ref "RSHUNT") (pin "2") (pinfunction "2_2") (pintype "passive"))
    )
    (net (code "38") (name "SHUNTL") (class "Default")
      (node (ref "K3") (pin "2") (pinfunction "2_2") (pintype "bidirectional"))
      (node (ref "RSHUNT") (pin "1") (pinfunction "1_1") (pintype "passive"))
      (node (ref "SEL_VCAP1") (pin "1") (pinfunction "1_1") (pintype "bidirectional"))
      (node (ref "SEL_VCAP2") (pin "1") (pinfunction "1_1") (pintype "bidirectional"))
    )
    (net (code "39") (name "SPI_CS") (class "Default")
      (node (ref "K1") (pin "18") (pinfunction "18_18") (pintype "bidirectional"))
      (node (ref "U1") (pin "M11") (pinfunction "PB12/SPI_CS_M11") (pintype "bidirectional"))
    )
    (net (code "40") (name "SPI_MISO") (class "Default")
      (node (ref "K1") (pin "13") (pinfunction "13_13") (pintype "bidirectional"))
      (node (ref "U1") (pin "L11") (pinfunction "PB14/SPI_MISO_L11") (pintype "bidirectional"))
    )
    (net (code "41") (name "SPI_MOSI") (class "Default")
      (node (ref "K1") (pin "14") (pinfunction "14_14") (pintype "bidirectional"))
      (node (ref "U1") (pin "L12") (pinfunction "PB15/SPI_MOSI_L12") (pintype "bidirectional"))
    )
    (net (code "42") (name "SPI_SCK") (class "Default")
      (node (ref "K1") (pin "12") (pinfunction "12_12") (pintype "bidirectional"))
      (node (ref "U1") (pin "M12") (pinfunction "PB13/SPI_SCK_M12") (pintype "bidirectional"))
    )
    (net (code "43") (name "UART_RX") (class "Default")
      (node (ref "K1") (pin "8") (pinfunction "8_8") (pintype "bidirectional"))
      (node (ref "U1") (pin "D11") (pinfunction "PA10/UART_RX_D11") (pintype "bidirectional"))
    )
    (net (code "44") (name "UART_TX") (class "Default")
      (node (ref "K1") (pin "7") (pinfunction "7_7") (pintype "bidirectional"))
      (node (ref "U1") (pin "D12") (pinfunction "PA9/UART_TX_D12") (pintype "bidirectional"))
    )
    (net (code "45") (name "VCAP1") (class "Default")
      (node (ref "SEL_VCAP1") (pin "2") (pinfunction "2_2") (pintype "bidirectional"))
      (node (ref "U1") (pin "H7") (pinfunction "VCAP1_H7") (pintype "passive"))
    )
    (net (code "46") (name "VCAP2") (class "Default")
      (node (ref "SEL_VCAP2") (pin "2") (pinfunction "2_2") (pintype "bidirectional"))
      (node (ref "U1") (pin "G9") (pinfunction "VCAP2_G9") (pintype "passive"))
    )
    (net (code "47") (name "unconnected-(K1-Pad1)") (class "Default")
      (node (ref "K1") (pin "1") (pinfunction "1_1") (pintype "bidirectional"))
    )
    (net (code "48") (name "unconnected-(K1-Pad5)") (class "Default")
      (node (ref "K1") (pin "5") (pinfunction "5_5") (pintype "bidirectional"))
    )
    (net (code "49") (name "unconnected-(K1-Pad19)") (class "Default")
      (node (ref "K1") (pin "19") (pinfunction "19_19") (pintype "bidirectional"))
    )
    (net (code "50") (name "unconnected-(K2-Pad15)") (class "Default")
      (node (ref "K2") (pin "15") (pinfunction "15_15") (pintype "bidirectional"))
    )
    (net (code "51") (name "unconnected-(K2-Pad16)") (class "Default")
      (node (ref "K2") (pin "16") (pinfunction "16_16") (pintype "bidirectional"))
    )
    (net (code "52") (name "unconnected-(K2-Pad17)") (class "Default")
      (node (ref "K2") (pin "17") (pinfunction "17_17") (pintype "bidirectional"))
    )
    (net (code "53") (name "unconnected-(K2-Pad18)") (class "Default")
      (node (ref "K2") (pin "18") (pinfunction "18_18") (pintype "bidirectional"))
    )
    (net (code "54") (name "unconnected-(K2-Pad19)") (class "Default")
      (node (ref "K2") (pin "19") (pinfunction "19_19") (pintype "bidirectional"))
    )
    (net (code "55") (name "unconnected-(K2-Pad20)") (class "Default")
      (node (ref "K2") (pin "20") (pinfunction "20_20") (pintype "bidirectional"))
    )
    (net (code "56") (name "unconnected-(K3-Pad12)") (class "Default")
      (node (ref "K3") (pin "12") (pinfunction "12_12") (pintype "bidirectional"))
    )
    (net (code "57") (name "unconnected-(K3-Pad13)") (class "Default")
      (node (ref "K3") (pin "13") (pinfunction "13_13") (pintype "bidirectional"))
    )
    (net (code "58") (name "unconnected-(K3-Pad15)") (class "Default")
      (node (ref "K3") (pin "15") (pinfunction "15_15") (pintype "bidirectional"))
    )
    (net (code "59") (name "unconnected-(STLINK_V2-Pad11)") (class "Default")
      (node (ref "STLINK_V2") (pin "11") (pinfunction "11_11") (pintype "bidirectional"))
    )
    (net (code "60") (name "unconnected-(STLINK_V2-Pad17)") (class "Default")
      (node (ref "STLINK_V2") (pin "17") (pinfunction "17_17") (pintype "bidirectional"))
    )
  )
)
